# SCH_ppc_2025-05-21.net
KiCad netlist of a schematic drawn in EasyEDA
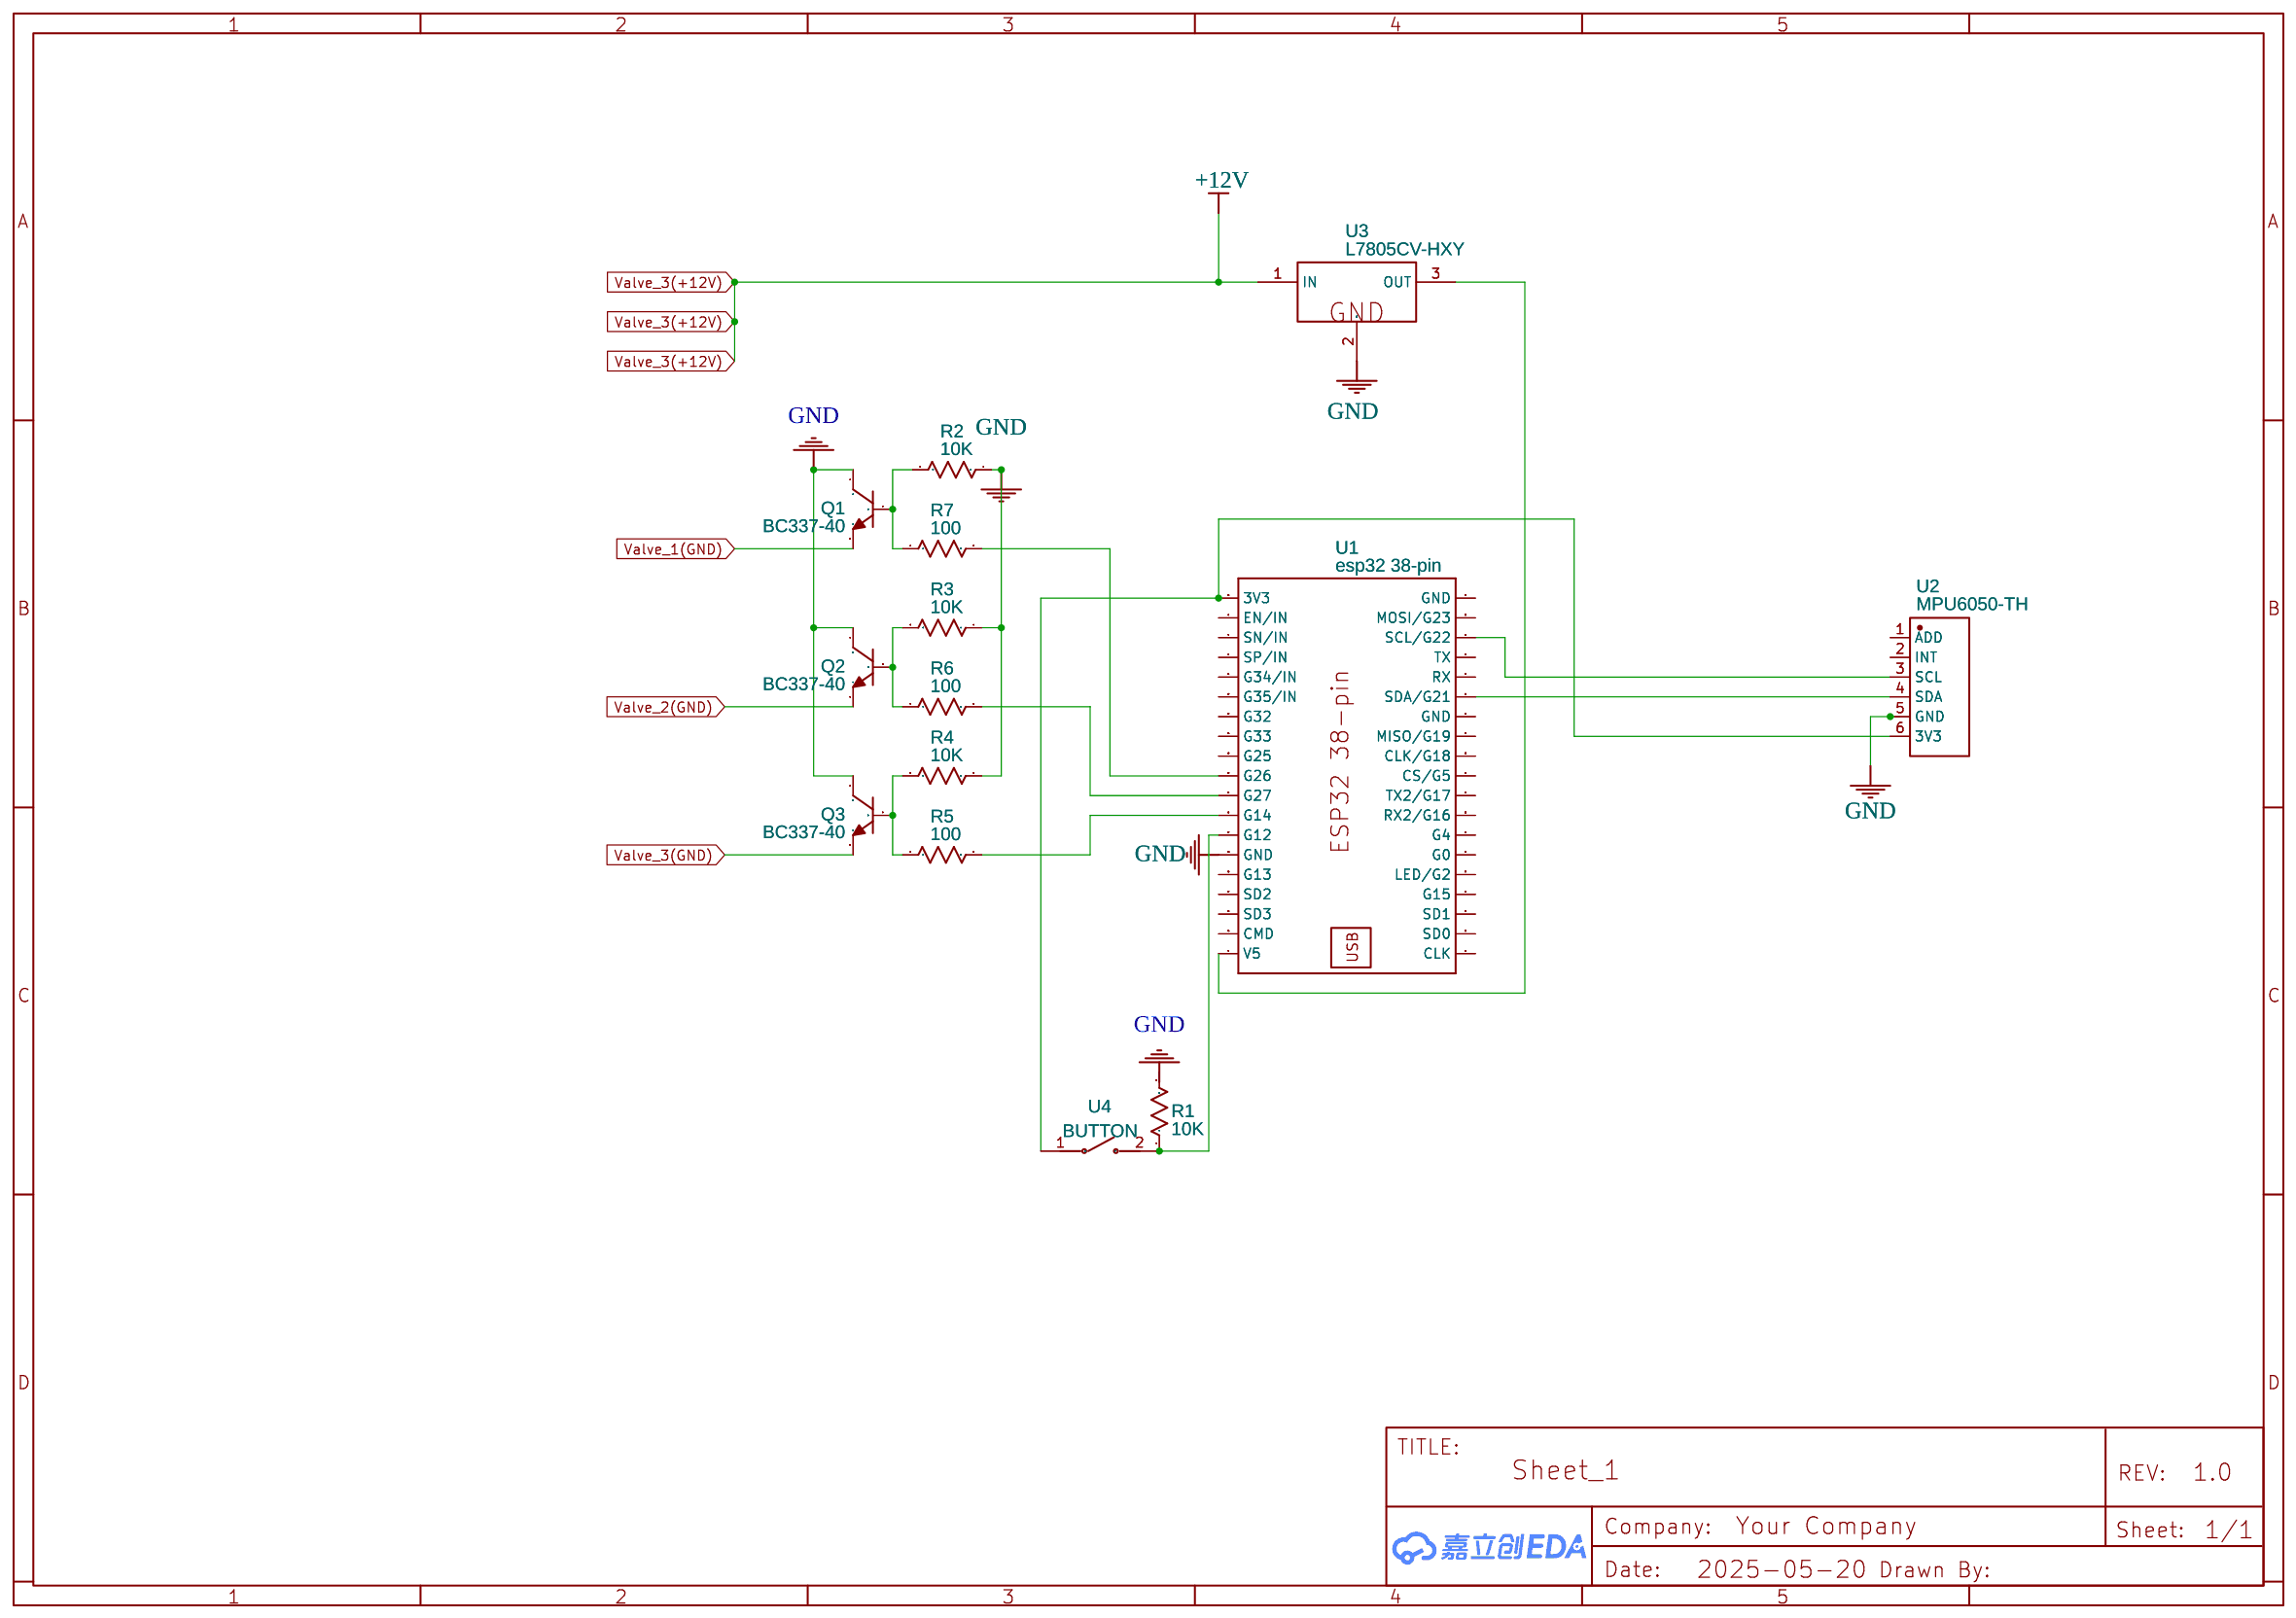
[diagram p0: schematic sheet]

(export (version "E")
  (design (tool "Eeschema 10.0.6"))
  (components
    (comp (ref "Q1")
      (value "BC337-40")
      (fields (field (name "Manufacturer") "LGE(鲁光)"))
      (libsource (lib "") (part "BC337-40"))
    )
    (comp (ref "Q2")
      (value "BC337-40")
      (fields (field (name "Manufacturer") "LGE(鲁光)"))
      (libsource (lib "") (part "BC337-40"))
    )
    (comp (ref "Q3")
      (value "BC337-40")
      (fields (field (name "Manufacturer") "LGE(鲁光)"))
      (libsource (lib "") (part "BC337-40"))
    )
    (comp (ref "R1")
      (value "10K")
      (fields
        (field (name "BOM_Manufacturer Part") "MCF 0.25W 10K")
        (field (name "BOM_Supplier Part") "9339116")
      )
      (libsource (lib "") (part "10K_1"))
    )
    (comp (ref "R2")
      (value "10K")
      (fields
        (field (name "BOM_Manufacturer Part") "MCF 0.25W 10K")
        (field (name "BOM_Supplier Part") "9339116")
      )
      (libsource (lib "") (part "10K"))
    )
    (comp (ref "R3")
      (value "10K")
      (fields
        (field (name "BOM_Manufacturer Part") "MCF 0.25W 10K")
        (field (name "BOM_Supplier Part") "9339116")
      )
      (libsource (lib "") (part "10K"))
    )
    (comp (ref "R4")
      (value "10K")
      (fields
        (field (name "BOM_Manufacturer Part") "MCF 0.25W 10K")
        (field (name "BOM_Supplier Part") "9339116")
      )
      (libsource (lib "") (part "10K"))
    )
    (comp (ref "R5")
      (value "100")
      (fields
        (field (name "BOM_Manufacturer Part") "MCF 0.25W 10K")
        (field (name "BOM_Supplier Part") "9339116")
      )
      (libsource (lib "") (part "100"))
    )
    (comp (ref "R6")
      (value "100")
      (fields
        (field (name "BOM_Manufacturer Part") "MCF 0.25W 10K")
        (field (name "BOM_Supplier Part") "9339116")
      )
      (libsource (lib "") (part "100"))
    )
    (comp (ref "R7")
      (value "100")
      (fields
        (field (name "BOM_Manufacturer Part") "MCF 0.25W 10K")
        (field (name "BOM_Supplier Part") "9339116")
      )
      (libsource (lib "") (part "100"))
    )
    (comp (ref "U1") (value "esp32 38-pin") (libsource (lib "") (part "esp32 38-pin")))
    (comp (ref "U2") (value "MPU6050-TH") (libsource (lib "") (part "MPU6050-TH")))
    (comp (ref "U3")
      (value "L7805CV-HXY")
      (fields (field (name "Manufacturer") "HXY MOSFET(华轩阳电子)"))
      (libsource (lib "") (part "L7805CV-HXY"))
    )
    (comp (ref "U4") (value "BUTTON") (libsource (lib "") (part "BUTTON")))
  )
  (nets
    (net (code "1") (name "GND") (class "Default")
      (node (ref "Q1") (pin "1") (pinfunction "C_1") (pintype "input"))
      (node (ref "Q2") (pin "1") (pinfunction "C_1") (pintype "input"))
      (node (ref "Q3") (pin "1") (pinfunction "C_1") (pintype "input"))
      (node (ref "R1") (pin "2") (pinfunction "2_2") (pintype "unspecified"))
      (node (ref "R2") (pin "1") (pinfunction "1_1") (pintype "unspecified"))
      (node (ref "R3") (pin "1") (pinfunction "1_1") (pintype "unspecified"))
      (node (ref "R4") (pin "1") (pinfunction "1_1") (pintype "unspecified"))
      (node (ref "U1") (pin "GND2") (pinfunction "GND_GND2") (pintype "passive"))
      (node (ref "U2") (pin "5") (pinfunction "GND_5") (pintype "unspecified"))
      (node (ref "U3") (pin "2") (pinfunction "GND_2") (pintype "passive"))
    )
    (net (code "2") (name "Net-(Q1-B)") (class "Default")
      (node (ref "Q1") (pin "2") (pinfunction "B_2") (pintype "input"))
      (node (ref "R2") (pin "2") (pinfunction "2_2") (pintype "unspecified"))
      (node (ref "R7") (pin "1") (pinfunction "1_1") (pintype "unspecified"))
    )
    (net (code "3") (name "Net-(Q2-B)") (class "Default")
      (node (ref "Q2") (pin "2") (pinfunction "B_2") (pintype "input"))
      (node (ref "R3") (pin "2") (pinfunction "2_2") (pintype "unspecified"))
      (node (ref "R6") (pin "1") (pinfunction "1_1") (pintype "unspecified"))
    )
    (net (code "4") (name "Net-(Q3-B)") (class "Default")
      (node (ref "Q3") (pin "2") (pinfunction "B_2") (pintype "input"))
      (node (ref "R4") (pin "2") (pinfunction "2_2") (pintype "unspecified"))
      (node (ref "R5") (pin "1") (pinfunction "1_1") (pintype "unspecified"))
    )
    (net (code "5") (name "Net-(U1-G12)") (class "Default")
      (node (ref "R1") (pin "1") (pinfunction "1_1") (pintype "unspecified"))
      (node (ref "U1") (pin "D12") (pinfunction "G12_D12") (pintype "bidirectional"))
      (node (ref "U4") (pin "2") (pinfunction "2_2") (pintype "unspecified"))
    )
    (net (code "6") (name "Net-(U1-G14)") (class "Default")
      (node (ref "R5") (pin "2") (pinfunction "2_2") (pintype "unspecified"))
      (node (ref "U1") (pin "D14") (pinfunction "G14_D14") (pintype "bidirectional"))
    )
    (net (code "7") (name "Net-(U1-G26)") (class "Default")
      (node (ref "R7") (pin "2") (pinfunction "2_2") (pintype "unspecified"))
      (node (ref "U1") (pin "D26") (pinfunction "G26_D26") (pintype "bidirectional"))
    )
    (net (code "8") (name "Net-(U1-G27)") (class "Default")
      (node (ref "R6") (pin "2") (pinfunction "2_2") (pintype "unspecified"))
      (node (ref "U1") (pin "D27") (pinfunction "G27_D27") (pintype "bidirectional"))
    )
    (net (code "9") (name "Net-(U1-SCL{slash}G22)") (class "Default")
      (node (ref "U1") (pin "D22") (pinfunction "SCL/G22_D22") (pintype "bidirectional"))
      (node (ref "U2") (pin "3") (pinfunction "SCL_3") (pintype "unspecified"))
    )
    (net (code "10") (name "Net-(U1-SDA{slash}G21)") (class "Default")
      (node (ref "U1") (pin "D21") (pinfunction "SDA/G21_D21") (pintype "bidirectional"))
      (node (ref "U2") (pin "4") (pinfunction "SDA_4") (pintype "unspecified"))
    )
    (net (code "11") (name "Net-(U2-3V3)") (class "Default")
      (node (ref "U1") (pin "3V3") (pinfunction "3V3_3V3") (pintype "passive"))
      (node (ref "U2") (pin "6") (pinfunction "3V3_6") (pintype "unspecified"))
      (node (ref "U4") (pin "1") (pinfunction "1_1") (pintype "unspecified"))
    )
    (net (code "12") (name "Net-(U3-OUT)") (class "Default")
      (node (ref "U1") (pin "V5") (pinfunction "V5_V5") (pintype "passive"))
      (node (ref "U3") (pin "3") (pinfunction "OUT_3") (pintype "passive"))
    )
    (net (code "13") (name "Valve_1(GND)") (class "Default")
      (node (ref "Q1") (pin "3") (pinfunction "E_3") (pintype "input"))
    )
    (net (code "14") (name "Valve_2(GND)") (class "Default")
      (node (ref "Q2") (pin "3") (pinfunction "E_3") (pintype "input"))
    )
    (net (code "15") (name "Valve_3(+12V)") (class "Default")
      (node (ref "U3") (pin "1") (pinfunction "IN_1") (pintype "passive"))
    )
    (net (code "16") (name "Valve_3(GND)") (class "Default")
      (node (ref "Q3") (pin "3") (pinfunction "E_3") (pintype "input"))
    )
    (net (code "17") (name "unconnected-(U1-CLK{slash}G18-PadD18)") (class "Default")
      (node (ref "U1") (pin "D18") (pinfunction "CLK/G18_D18") (pintype "bidirectional"))
    )
    (net (code "18") (name "unconnected-(U1-CS{slash}G5-PadD5)") (class "Default")
      (node (ref "U1") (pin "D5") (pinfunction "CS/G5_D5") (pintype "bidirectional"))
    )
    (net (code "19") (name "unconnected-(U1-EN{slash}IN-PadEN)") (class "Default")
      (node (ref "U1") (pin "EN") (pinfunction "EN/IN_EN") (pintype "unspecified"))
    )
    (net (code "20") (name "unconnected-(U1-G0-PadD0)") (class "Default")
      (node (ref "U1") (pin "D0") (pinfunction "G0_D0") (pintype "bidirectional"))
    )
    (net (code "21") (name "unconnected-(U1-G4-PadD4)") (class "Default")
      (node (ref "U1") (pin "D4") (pinfunction "G4_D4") (pintype "bidirectional"))
    )
    (net (code "22") (name "unconnected-(U1-G13-PadD13)") (class "Default")
      (node (ref "U1") (pin "D13") (pinfunction "G13_D13") (pintype "bidirectional"))
    )
    (net (code "23") (name "unconnected-(U1-G15-PadD15)") (class "Default")
      (node (ref "U1") (pin "D15") (pinfunction "G15_D15") (pintype "bidirectional"))
    )
    (net (code "24") (name "unconnected-(U1-G25-PadD25)") (class "Default")
      (node (ref "U1") (pin "D25") (pinfunction "G25_D25") (pintype "bidirectional"))
    )
    (net (code "25") (name "unconnected-(U1-G32-PadD32)") (class "Default")
      (node (ref "U1") (pin "D32") (pinfunction "G32_D32") (pintype "bidirectional"))
    )
    (net (code "26") (name "unconnected-(U1-G33-PadD33)") (class "Default")
      (node (ref "U1") (pin "D33") (pinfunction "G33_D33") (pintype "bidirectional"))
    )
    (net (code "27") (name "unconnected-(U1-G34{slash}IN-PadD34)") (class "Default")
      (node (ref "U1") (pin "D34") (pinfunction "G34/IN_D34") (pintype "input"))
    )
    (net (code "28") (name "unconnected-(U1-G35{slash}IN-PadD35)") (class "Default")
      (node (ref "U1") (pin "D35") (pinfunction "G35/IN_D35") (pintype "input"))
    )
    (net (code "29") (name "unconnected-(U1-GND-PadGND1)") (class "Default")
      (node (ref "U1") (pin "GND1") (pinfunction "GND_GND1") (pintype "passive"))
    )
    (net (code "30") (name "unconnected-(U1-LED{slash}G2-PadD2)") (class "Default")
      (node (ref "U1") (pin "D2") (pinfunction "LED/G2_D2") (pintype "bidirectional"))
    )
    (net (code "31") (name "unconnected-(U1-MISO{slash}G19-PadD19)") (class "Default")
      (node (ref "U1") (pin "D19") (pinfunction "MISO/G19_D19") (pintype "bidirectional"))
    )
    (net (code "32") (name "unconnected-(U1-MOSI{slash}G23-PadD23)") (class "Default")
      (node (ref "U1") (pin "D23") (pinfunction "MOSI/G23_D23") (pintype "bidirectional"))
    )
    (net (code "33") (name "unconnected-(U1-PadCLK)") (class "Default")
      (node (ref "U1") (pin "CLK") (pinfunction "CLK_CLK") (pintype "unspecified"))
    )
    (net (code "34") (name "unconnected-(U1-PadCMD)") (class "Default")
      (node (ref "U1") (pin "CMD") (pinfunction "CMD_CMD") (pintype "unspecified"))
    )
    (net (code "35") (name "unconnected-(U1-PadGND)") (class "Default")
      (node (ref "U1") (pin "GND") (pinfunction "GND_GND") (pintype "passive"))
    )
    (net (code "36") (name "unconnected-(U1-PadRX)") (class "Default")
      (node (ref "U1") (pin "RX") (pinfunction "RX_RX") (pintype "unspecified"))
    )
    (net (code "37") (name "unconnected-(U1-PadSD0)") (class "Default")
      (node (ref "U1") (pin "SD0") (pinfunction "SD0_SD0") (pintype "unspecified"))
    )
    (net (code "38") (name "unconnected-(U1-PadSD1)") (class "Default")
      (node (ref "U1") (pin "SD1") (pinfunction "SD1_SD1") (pintype "unspecified"))
    )
    (net (code "39") (name "unconnected-(U1-PadSD2)") (class "Default")
      (node (ref "U1") (pin "SD2") (pinfunction "SD2_SD2") (pintype "unspecified"))
    )
    (net (code "40") (name "unconnected-(U1-PadSD3)") (class "Default")
      (node (ref "U1") (pin "SD3") (pinfunction "SD3_SD3") (pintype "unspecified"))
    )
    (net (code "41") (name "unconnected-(U1-PadTX)") (class "Default")
      (node (ref "U1") (pin "TX") (pinfunction "TX_TX") (pintype "unspecified"))
    )
    (net (code "42") (name "unconnected-(U1-RX2{slash}G16-PadD16)") (class "Default")
      (node (ref "U1") (pin "D16") (pinfunction "RX2/G16_D16") (pintype "bidirectional"))
    )
    (net (code "43") (name "unconnected-(U1-SN{slash}IN-PadVP)") (class "Default")
      (node (ref "U1") (pin "VP") (pinfunction "SN/IN_VP") (pintype "input"))
    )
    (net (code "44") (name "unconnected-(U1-SP{slash}IN-PadVN)") (class "Default")
      (node (ref "U1") (pin "VN") (pinfunction "SP/IN_VN") (pintype "input"))
    )
    (net (code "45") (name "unconnected-(U1-TX2{slash}G17-PadD17)") (class "Default")
      (node (ref "U1") (pin "D17") (pinfunction "TX2/G17_D17") (pintype "bidirectional"))
    )
    (net (code "46") (name "unconnected-(U2-ADD-Pad1)") (class "Default")
      (node (ref "U2") (pin "1") (pinfunction "ADD_1") (pintype "unspecified"))
    )
    (net (code "47") (name "unconnected-(U2-INT-Pad2)") (class "Default")
      (node (ref "U2") (pin "2") (pinfunction "INT_2") (pintype "unspecified"))
    )
  )
)
